# carte.net
KiCad netlist of a schematic drawn in Altium Designer
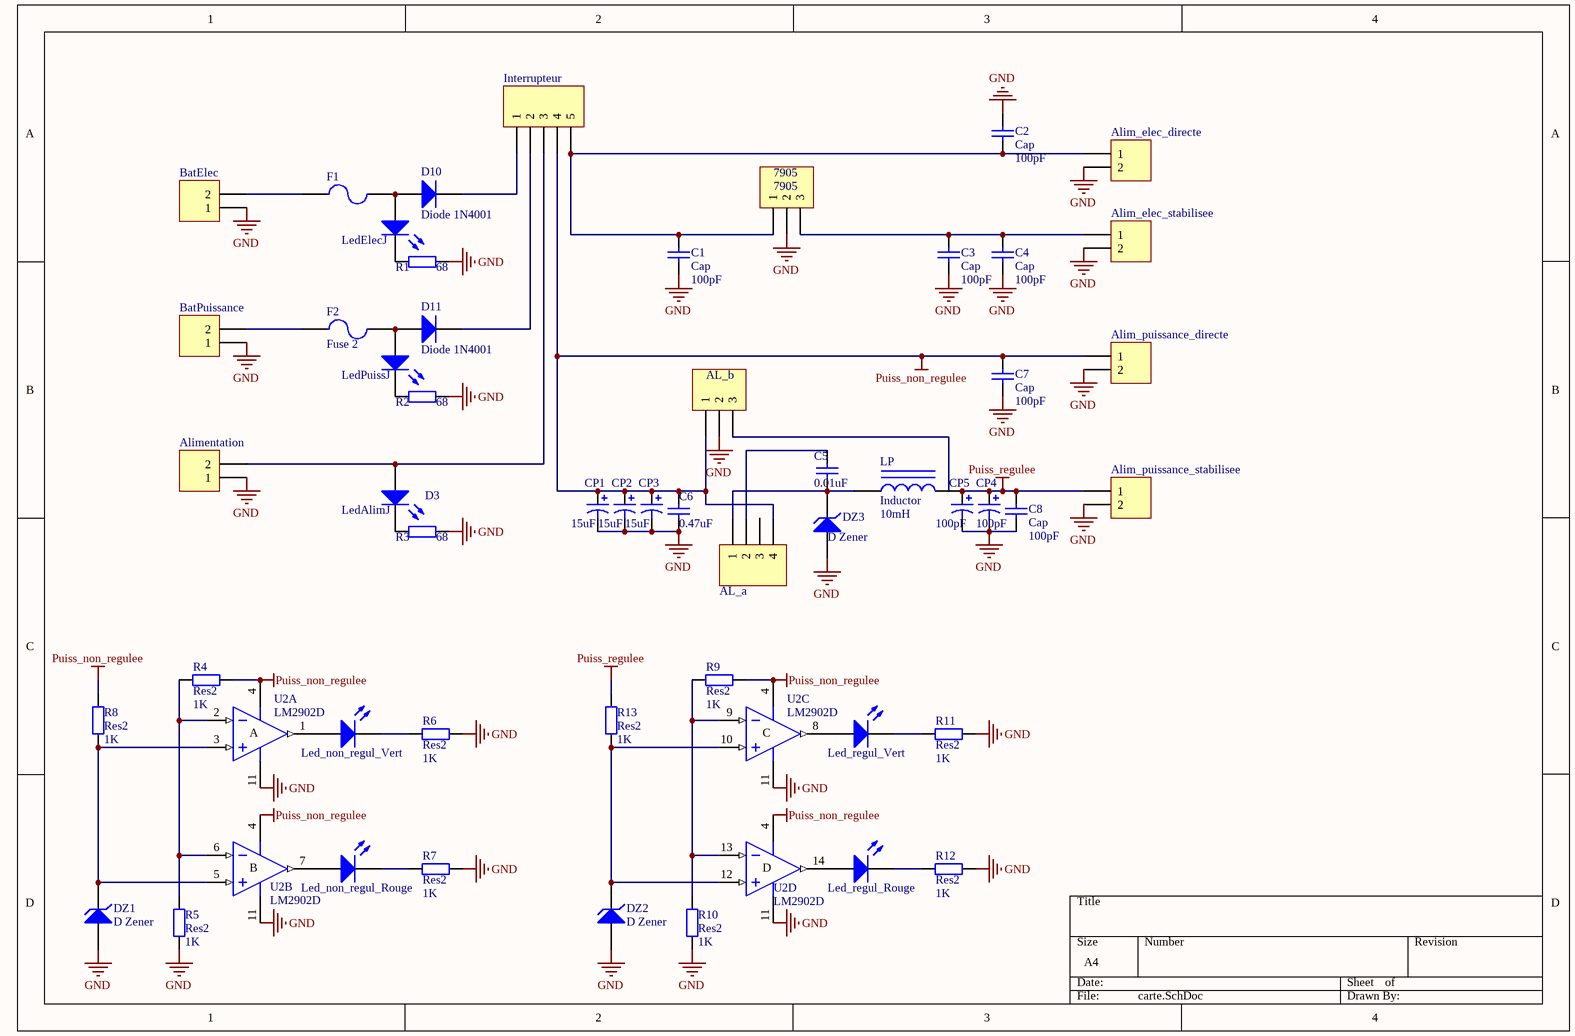
[diagram p0: carte.SchDoc]

(export (version "E")
  (design (tool "Eeschema 10.0.6"))
  (components
    (comp (ref "7905")
      (value "7905")
      (footprint "MHDR1X3")
      (description "Header, 3-Pin")
      (fields (field (name "PUBLISHER") "Altium Limited"))
      (libsource (lib "Miscellaneous Connectors") (part "MHDR1X3"))
    )
    (comp (ref "Alimentation")
      (value "Header 2")
      (footprint "HDR1X2")
      (description "Header, 2-Pin")
      (fields (field (name "PUBLISHER") "Altium Limited"))
      (libsource (lib "") (part "Header 2_1"))
    )
    (comp (ref "Alim_elec_directe")
      (value "Header 2")
      (footprint "HDR1X2")
      (description "Header, 2-Pin")
      (fields (field (name "PUBLISHER") "Altium Limited"))
      (libsource (lib "Miscellaneous Connectors") (part "Header 2"))
    )
    (comp (ref "Alim_elec_stabilisee")
      (value "Header 2")
      (footprint "HDR1X2")
      (description "Header, 2-Pin")
      (fields (field (name "PUBLISHER") "Altium Limited"))
      (libsource (lib "Miscellaneous Connectors") (part "Header 2"))
    )
    (comp (ref "Alim_puissance_directe")
      (value "Header 2")
      (footprint "HDR1X2")
      (description "Header, 2-Pin")
      (fields (field (name "PUBLISHER") "Altium Limited"))
      (libsource (lib "Miscellaneous Connectors") (part "Header 2"))
    )
    (comp (ref "Alim_puissance_stabilisee")
      (value "Header 2")
      (footprint "HDR1X2")
      (description "Header, 2-Pin")
      (fields (field (name "PUBLISHER") "Altium Limited"))
      (libsource (lib "Miscellaneous Connectors") (part "Header 2"))
    )
    (comp (ref "AL_a")
      (value "Header 4")
      (footprint "HDR1X4")
      (description "Header, 4-Pin")
      (fields (field (name "PUBLISHER") "Altium Limited"))
      (libsource (lib "Miscellaneous Connectors") (part "Header 4"))
    )
    (comp (ref "AL_b")
      (value "Header 3")
      (footprint "HDR1X3")
      (description "Header, 3-Pin")
      (fields (field (name "PUBLISHER") "Altium Limited"))
      (libsource (lib "Miscellaneous Connectors") (part "Header 3"))
    )
    (comp (ref "BatElec")
      (value "Header 2")
      (footprint "HDR1X2")
      (description "Header, 2-Pin")
      (fields (field (name "PUBLISHER") "Altium Limited"))
      (libsource (lib "") (part "Header 2_1"))
    )
    (comp (ref "BatPuissance")
      (value "Header 2")
      (footprint "HDR1X2")
      (description "Header, 2-Pin")
      (fields (field (name "PUBLISHER") "Altium Limited"))
      (libsource (lib "") (part "Header 2_1"))
    )
    (comp (ref "C1")
      (value "Cap")
      (footprint "RAD-0.3")
      (description "Capacitor")
      (fields (field (name "ALTIUM_VALUE") "100pF") (field (name "PUBLISHER") "Altium Limited"))
      (libsource (lib "Miscellaneous Devices") (part "Cap"))
    )
    (comp (ref "C2")
      (value "Cap")
      (footprint "RAD-0.3")
      (description "Capacitor")
      (fields (field (name "ALTIUM_VALUE") "100pF") (field (name "PUBLISHER") "Altium Limited"))
      (libsource (lib "Miscellaneous Devices") (part "Cap"))
    )
    (comp (ref "C3")
      (value "Cap")
      (footprint "RAD-0.3")
      (description "Capacitor")
      (fields (field (name "ALTIUM_VALUE") "100pF") (field (name "PUBLISHER") "Altium Limited"))
      (libsource (lib "Miscellaneous Devices") (part "Cap"))
    )
    (comp (ref "C4")
      (value "Cap")
      (footprint "RAD-0.3")
      (description "Capacitor")
      (fields (field (name "ALTIUM_VALUE") "100pF") (field (name "PUBLISHER") "Altium Limited"))
      (libsource (lib "Miscellaneous Devices") (part "Cap"))
    )
    (comp (ref "C5")
      (value "0.01uF")
      (footprint "RAD-0.3")
      (description "Capacitor")
      (fields (field (name "Comment") "Cap") (field (name "PUBLISHER") "Altium Limited"))
      (libsource (lib "Miscellaneous Devices") (part "Cap"))
    )
    (comp (ref "C6")
      (value "0.47uF")
      (footprint "RAD-0.3")
      (description "Capacitor")
      (fields (field (name "Comment") "Cap") (field (name "PUBLISHER") "Altium Limited"))
      (libsource (lib "Miscellaneous Devices") (part "Cap"))
    )
    (comp (ref "C7")
      (value "Cap")
      (footprint "RAD-0.3")
      (description "Capacitor")
      (fields (field (name "ALTIUM_VALUE") "100pF") (field (name "PUBLISHER") "Altium Limited"))
      (libsource (lib "Miscellaneous Devices") (part "Cap"))
    )
    (comp (ref "C8")
      (value "Cap")
      (footprint "RAD-0.3")
      (description "Capacitor")
      (fields (field (name "ALTIUM_VALUE") "100pF") (field (name "PUBLISHER") "Altium Limited"))
      (libsource (lib "Miscellaneous Devices") (part "Cap"))
    )
    (comp (ref "CP1")
      (value "15uF")
      (footprint "RB7.6-15")
      (description "Polarized Capacitor (Radial)")
      (fields (field (name "Comment") "Cap Pol1") (field (name "PUBLISHER") "Altium Limited"))
      (libsource (lib "Miscellaneous Devices") (part "Cap Pol1"))
    )
    (comp (ref "CP2")
      (value "15uF")
      (footprint "RB7.6-15")
      (description "Polarized Capacitor (Radial)")
      (fields (field (name "Comment") "Cap Pol1") (field (name "PUBLISHER") "Altium Limited"))
      (libsource (lib "Miscellaneous Devices") (part "Cap Pol1"))
    )
    (comp (ref "CP3")
      (value "15uF")
      (footprint "RB7.6-15")
      (description "Polarized Capacitor (Radial)")
      (fields (field (name "Comment") "Cap Pol1") (field (name "PUBLISHER") "Altium Limited"))
      (libsource (lib "Miscellaneous Devices") (part "Cap Pol1"))
    )
    (comp (ref "CP4")
      (value "100pF")
      (footprint "RB7.6-15")
      (description "Polarized Capacitor (Radial)")
      (fields (field (name "Comment") "Cap Pol1") (field (name "PUBLISHER") "Altium Limited"))
      (libsource (lib "Miscellaneous Devices") (part "Cap Pol1"))
    )
    (comp (ref "CP5")
      (value "100pF")
      (footprint "RB7.6-15")
      (description "Polarized Capacitor (Radial)")
      (fields (field (name "Comment") "Cap Pol1") (field (name "PUBLISHER") "Altium Limited"))
      (libsource (lib "Miscellaneous Devices") (part "Cap Pol1"))
    )
    (comp (ref "D3")
      (value "LedAlimJ")
      (footprint "LED-1")
      (description "Typical RED GaAs LED")
      (fields (field (name "PUBLISHER") "Altium Limited"))
      (libsource (lib "Miscellaneous Devices") (part "LED1"))
    )
    (comp (ref "D10")
      (value "Diode 1N4001")
      (footprint "DO-41")
      (description "1 Amp General Purpose Rectifier")
      (fields (field (name "PUBLISHER") "Altium Limited"))
      (libsource (lib "Miscellaneous Devices") (part "Diode 1N4001"))
    )
    (comp (ref "D11")
      (value "Diode 1N4001")
      (footprint "DO-41")
      (description "1 Amp General Purpose Rectifier")
      (fields (field (name "PUBLISHER") "Altium Limited"))
      (libsource (lib "Miscellaneous Devices") (part "Diode 1N4001"))
    )
    (comp (ref "DZ1")
      (value "D Zener")
      (footprint "DIODE-0.7")
      (description "Zener Diode")
      (fields (field (name "PUBLISHER") "Altium Limited"))
      (libsource (lib "Miscellaneous Devices") (part "D Zener"))
    )
    (comp (ref "DZ2")
      (value "D Zener")
      (footprint "DIODE-0.7")
      (description "Zener Diode")
      (fields (field (name "PUBLISHER") "Altium Limited"))
      (libsource (lib "Miscellaneous Devices") (part "D Zener"))
    )
    (comp (ref "DZ3")
      (value "D Zener")
      (footprint "DIODE-0.7")
      (description "Zener Diode")
      (fields (field (name "PUBLISHER") "Altium Limited"))
      (libsource (lib "Miscellaneous Devices") (part "D Zener"))
    )
    (comp (ref "F1")
      (value "Fuse 2")
      (footprint "PIN-W2/E2.8")
      (description "Fuse")
      (fields (field (name "PUBLISHER") "Altium Limited"))
      (libsource (lib "Miscellaneous Devices") (part "Fuse 2"))
    )
    (comp (ref "F2")
      (value "Fuse 2")
      (footprint "PIN-W2/E2.8")
      (description "Fuse")
      (fields (field (name "PUBLISHER") "Altium Limited"))
      (libsource (lib "Miscellaneous Devices") (part "Fuse 2"))
    )
    (comp (ref "Interrupteur")
      (value "Header 5")
      (footprint "HDR1X5")
      (description "Header, 5-Pin")
      (fields (field (name "PUBLISHER") "Altium Limited"))
      (libsource (lib "Miscellaneous Connectors") (part "Header 5"))
    )
    (comp (ref "LedElecJ")
      (value "LED1")
      (footprint "LED-1")
      (description "Typical RED GaAs LED")
      (fields (field (name "PUBLISHER") "Altium Limited"))
      (libsource (lib "Miscellaneous Devices") (part "LED1"))
    )
    (comp (ref "LedPuissJ")
      (value "LED1")
      (footprint "LED-1")
      (description "Typical RED GaAs LED")
      (fields (field (name "PUBLISHER") "Altium Limited"))
      (libsource (lib "Miscellaneous Devices") (part "LED1"))
    )
    (comp (ref "Led_non_regul_Rouge")
      (value "LED1")
      (footprint "LED-1")
      (description "Typical RED GaAs LED")
      (fields (field (name "PUBLISHER") "Altium Limited"))
      (libsource (lib "Miscellaneous Devices") (part "LED1"))
    )
    (comp (ref "Led_non_regul_Vert")
      (value "LED1")
      (footprint "LED-1")
      (description "Typical RED GaAs LED")
      (fields (field (name "PUBLISHER") "Altium Limited"))
      (libsource (lib "Miscellaneous Devices") (part "LED1"))
    )
    (comp (ref "Led_regul_Rouge")
      (value "LED1")
      (footprint "LED-1")
      (description "Typical RED GaAs LED")
      (fields (field (name "PUBLISHER") "Altium Limited"))
      (libsource (lib "Miscellaneous Devices") (part "LED1"))
    )
    (comp (ref "Led_regul_Vert")
      (value "LED1")
      (footprint "LED-1")
      (description "Typical RED GaAs LED")
      (fields (field (name "PUBLISHER") "Altium Limited"))
      (libsource (lib "Miscellaneous Devices") (part "LED1"))
    )
    (comp (ref "LP")
      (value "Inductor")
      (footprint "AXIAL-0.9")
      (description "Magnetic-Core Inductor")
      (fields (field (name "ALTIUM_VALUE") "10mH") (field (name "PUBLISHER") "Altium Limited"))
      (libsource (lib "Miscellaneous Devices") (part "Inductor Iron"))
    )
    (comp (ref "R1")
      (value "68")
      (footprint "AXIAL-0.4")
      (description "Resistor")
      (fields (field (name "Comment") "Res2") (field (name "PUBLISHER") "Altium Limited"))
      (libsource (lib "Miscellaneous Devices") (part "Res2"))
    )
    (comp (ref "R2")
      (value "68")
      (footprint "AXIAL-0.4")
      (description "Resistor")
      (fields (field (name "Comment") "Res2") (field (name "PUBLISHER") "Altium Limited"))
      (libsource (lib "Miscellaneous Devices") (part "Res2"))
    )
    (comp (ref "R3")
      (value "68")
      (footprint "AXIAL-0.4")
      (description "Resistor")
      (fields (field (name "Comment") "Res2") (field (name "PUBLISHER") "Altium Limited"))
      (libsource (lib "Miscellaneous Devices") (part "Res2"))
    )
    (comp (ref "R4")
      (value "Res2")
      (footprint "AXIAL-0.4")
      (description "Resistor")
      (fields (field (name "ALTIUM_VALUE") "1K") (field (name "PUBLISHER") "Altium Limited"))
      (libsource (lib "") (part "Res2_1"))
    )
    (comp (ref "R5")
      (value "Res2")
      (footprint "AXIAL-0.4")
      (description "Resistor")
      (fields (field (name "ALTIUM_VALUE") "1K") (field (name "PUBLISHER") "Altium Limited"))
      (libsource (lib "") (part "Res2_2"))
    )
    (comp (ref "R6")
      (value "Res2")
      (footprint "AXIAL-0.4")
      (description "Resistor")
      (fields (field (name "ALTIUM_VALUE") "1K") (field (name "PUBLISHER") "Altium Limited"))
      (libsource (lib "Miscellaneous Devices") (part "Res2"))
    )
    (comp (ref "R7")
      (value "Res2")
      (footprint "AXIAL-0.4")
      (description "Resistor")
      (fields (field (name "ALTIUM_VALUE") "1K") (field (name "PUBLISHER") "Altium Limited"))
      (libsource (lib "Miscellaneous Devices") (part "Res2"))
    )
    (comp (ref "R8")
      (value "Res2")
      (footprint "AXIAL-0.4")
      (description "Resistor")
      (fields (field (name "ALTIUM_VALUE") "1K") (field (name "PUBLISHER") "Altium Limited"))
      (libsource (lib "") (part "Res2_2"))
    )
    (comp (ref "R9")
      (value "Res2")
      (footprint "AXIAL-0.4")
      (description "Resistor")
      (fields (field (name "ALTIUM_VALUE") "1K") (field (name "PUBLISHER") "Altium Limited"))
      (libsource (lib "") (part "Res2_1"))
    )
    (comp (ref "R10")
      (value "Res2")
      (footprint "AXIAL-0.4")
      (description "Resistor")
      (fields (field (name "ALTIUM_VALUE") "1K") (field (name "PUBLISHER") "Altium Limited"))
      (libsource (lib "") (part "Res2_2"))
    )
    (comp (ref "R11")
      (value "Res2")
      (footprint "AXIAL-0.4")
      (description "Resistor")
      (fields (field (name "ALTIUM_VALUE") "1K") (field (name "PUBLISHER") "Altium Limited"))
      (libsource (lib "Miscellaneous Devices") (part "Res2"))
    )
    (comp (ref "R12")
      (value "Res2")
      (footprint "AXIAL-0.4")
      (description "Resistor")
      (fields (field (name "ALTIUM_VALUE") "1K") (field (name "PUBLISHER") "Altium Limited"))
      (libsource (lib "Miscellaneous Devices") (part "Res2"))
    )
    (comp (ref "R13")
      (value "Res2")
      (footprint "AXIAL-0.4")
      (description "Resistor")
      (fields (field (name "ALTIUM_VALUE") "1K") (field (name "PUBLISHER") "Altium Limited"))
      (libsource (lib "") (part "Res2_2"))
    )
    (comp (ref "U2")
      (value "LM2902D")
      (footprint "D014_N")
      (description "Quadruple Operational Amplifier")
      (fields (field (name "PUBLISHER") "Altium Limited"))
      (libsource (lib "TI Operational Amplifier") (part "LM2902D"))
    )
  )
  (nets
    (net (code "1") (name "GND") (class "Default")
      (node (ref "7905") (pin "2") (pinfunction "2_2") (pintype "passive"))
      (node (ref "AL_b") (pin "2") (pinfunction "2_2") (pintype "passive"))
      (node (ref "Alim_elec_directe") (pin "2") (pinfunction "2_2") (pintype "passive"))
      (node (ref "Alim_elec_stabilisee") (pin "2") (pinfunction "2_2") (pintype "passive"))
      (node (ref "Alim_puissance_directe") (pin "2") (pinfunction "2_2") (pintype "passive"))
      (node (ref "Alim_puissance_stabilisee") (pin "2") (pinfunction "2_2") (pintype "passive"))
      (node (ref "Alimentation") (pin "1") (pinfunction "1_1") (pintype "passive"))
      (node (ref "BatElec") (pin "1") (pinfunction "1_1") (pintype "passive"))
      (node (ref "BatPuissance") (pin "1") (pinfunction "1_1") (pintype "passive"))
      (node (ref "C1") (pin "1") (pinfunction "1_1") (pintype "passive"))
      (node (ref "C2") (pin "2") (pinfunction "2_2") (pintype "passive"))
      (node (ref "C3") (pin "1") (pinfunction "1_1") (pintype "passive"))
      (node (ref "C4") (pin "1") (pinfunction "1_1") (pintype "passive"))
      (node (ref "C6") (pin "1") (pinfunction "1_1") (pintype "passive"))
      (node (ref "C7") (pin "1") (pinfunction "1_1") (pintype "passive"))
      (node (ref "C8") (pin "1") (pinfunction "1_1") (pintype "passive"))
      (node (ref "CP1") (pin "2") (pinfunction "2_2") (pintype "passive"))
      (node (ref "CP2") (pin "2") (pinfunction "2_2") (pintype "passive"))
      (node (ref "CP3") (pin "2") (pinfunction "2_2") (pintype "passive"))
      (node (ref "CP4") (pin "2") (pinfunction "2_2") (pintype "passive"))
      (node (ref "CP5") (pin "2") (pinfunction "2_2") (pintype "passive"))
      (node (ref "DZ1") (pin "1") (pinfunction "A_1") (pintype "passive"))
      (node (ref "DZ2") (pin "1") (pinfunction "A_1") (pintype "passive"))
      (node (ref "DZ3") (pin "1") (pinfunction "A_1") (pintype "passive"))
      (node (ref "R1") (pin "2") (pinfunction "2_2") (pintype "passive"))
      (node (ref "R10") (pin "1") (pinfunction "1_1") (pintype "passive"))
      (node (ref "R11") (pin "2") (pinfunction "2_2") (pintype "passive"))
      (node (ref "R12") (pin "2") (pinfunction "2_2") (pintype "passive"))
      (node (ref "R2") (pin "2") (pinfunction "2_2") (pintype "passive"))
      (node (ref "R3") (pin "2") (pinfunction "2_2") (pintype "passive"))
      (node (ref "R5") (pin "1") (pinfunction "1_1") (pintype "passive"))
      (node (ref "R6") (pin "2") (pinfunction "2_2") (pintype "passive"))
      (node (ref "R7") (pin "2") (pinfunction "2_2") (pintype "passive"))
      (node (ref "U2") (pin "11") (pinfunction "V-_11") (pintype "power_in"))
    )
    (net (code "2") (name "Net-(7905-Pad1)") (class "Default")
      (node (ref "7905") (pin "1") (pinfunction "1_1") (pintype "passive"))
      (node (ref "Alim_elec_directe") (pin "1") (pinfunction "1_1") (pintype "passive"))
      (node (ref "C1") (pin "2") (pinfunction "2_2") (pintype "passive"))
      (node (ref "C2") (pin "1") (pinfunction "1_1") (pintype "passive"))
      (node (ref "Interrupteur") (pin "5") (pinfunction "5_5") (pintype "passive"))
    )
    (net (code "3") (name "Net-(7905-Pad3)") (class "Default")
      (node (ref "7905") (pin "3") (pinfunction "3_3") (pintype "passive"))
      (node (ref "Alim_elec_stabilisee") (pin "1") (pinfunction "1_1") (pintype "passive"))
      (node (ref "C3") (pin "2") (pinfunction "2_2") (pintype "passive"))
      (node (ref "C4") (pin "2") (pinfunction "2_2") (pintype "passive"))
    )
    (net (code "4") (name "Net-(AL_a-1)") (class "Default")
      (node (ref "AL_a") (pin "4") (pinfunction "1_4") (pintype "passive"))
      (node (ref "C5") (pin "1") (pinfunction "1_1") (pintype "passive"))
      (node (ref "DZ3") (pin "2") (pinfunction "K_2") (pintype "passive"))
      (node (ref "LP") (pin "1") (pinfunction "1_1") (pintype "passive"))
    )
    (net (code "5") (name "Net-(AL_a-2)") (class "Default")
      (node (ref "AL_a") (pin "3") (pinfunction "2_3") (pintype "passive"))
      (node (ref "C5") (pin "2") (pinfunction "2_2") (pintype "passive"))
    )
    (net (code "6") (name "Net-(BatElec-Pad2)") (class "Default")
      (node (ref "BatElec") (pin "2") (pinfunction "2_2") (pintype "passive"))
      (node (ref "F1") (pin "1") (pinfunction "1_1") (pintype "passive"))
    )
    (net (code "7") (name "Net-(BatPuissance-Pad2)") (class "Default")
      (node (ref "BatPuissance") (pin "2") (pinfunction "2_2") (pintype "passive"))
      (node (ref "F2") (pin "1") (pinfunction "1_1") (pintype "passive"))
    )
    (net (code "8") (name "Net-(D3-A)") (class "Default")
      (node (ref "Alimentation") (pin "2") (pinfunction "2_2") (pintype "passive"))
      (node (ref "D3") (pin "1") (pinfunction "A_1") (pintype "passive"))
      (node (ref "Interrupteur") (pin "3") (pinfunction "3_3") (pintype "passive"))
    )
    (net (code "9") (name "Net-(D3-K)") (class "Default")
      (node (ref "D3") (pin "2") (pinfunction "K_2") (pintype "passive"))
      (node (ref "R3") (pin "1") (pinfunction "1_1") (pintype "passive"))
    )
    (net (code "10") (name "Net-(D10-A)") (class "Default")
      (node (ref "D10") (pin "1") (pinfunction "A_1") (pintype "passive"))
      (node (ref "F1") (pin "2") (pinfunction "2_2") (pintype "passive"))
      (node (ref "LedElecJ") (pin "1") (pinfunction "A_1") (pintype "passive"))
    )
    (net (code "11") (name "Net-(D10-K)") (class "Default")
      (node (ref "D10") (pin "2") (pinfunction "K_2") (pintype "passive"))
      (node (ref "Interrupteur") (pin "1") (pinfunction "1_1") (pintype "passive"))
    )
    (net (code "12") (name "Net-(D11-A)") (class "Default")
      (node (ref "D11") (pin "1") (pinfunction "A_1") (pintype "passive"))
      (node (ref "F2") (pin "2") (pinfunction "2_2") (pintype "passive"))
      (node (ref "LedPuissJ") (pin "1") (pinfunction "A_1") (pintype "passive"))
    )
    (net (code "13") (name "Net-(D11-K)") (class "Default")
      (node (ref "D11") (pin "2") (pinfunction "K_2") (pintype "passive"))
      (node (ref "Interrupteur") (pin "2") (pinfunction "2_2") (pintype "passive"))
    )
    (net (code "14") (name "Net-(DZ1-K)") (class "Default")
      (node (ref "DZ1") (pin "2") (pinfunction "K_2") (pintype "passive"))
      (node (ref "R8") (pin "1") (pinfunction "1_1") (pintype "passive"))
      (node (ref "U2") (pin "3") (pinfunction "IN+_3") (pintype "input"))
      (node (ref "U2") (pin "5") (pinfunction "IN+_5") (pintype "input"))
    )
    (net (code "15") (name "Net-(DZ2-K)") (class "Default")
      (node (ref "DZ2") (pin "2") (pinfunction "K_2") (pintype "passive"))
      (node (ref "R13") (pin "1") (pinfunction "1_1") (pintype "passive"))
      (node (ref "U2") (pin "10") (pinfunction "IN+_10") (pintype "input"))
      (node (ref "U2") (pin "12") (pinfunction "IN+_12") (pintype "input"))
    )
    (net (code "16") (name "Net-(LedElecJ-K)") (class "Default")
      (node (ref "LedElecJ") (pin "2") (pinfunction "K_2") (pintype "passive"))
      (node (ref "R1") (pin "1") (pinfunction "1_1") (pintype "passive"))
    )
    (net (code "17") (name "Net-(LedPuissJ-K)") (class "Default")
      (node (ref "LedPuissJ") (pin "2") (pinfunction "K_2") (pintype "passive"))
      (node (ref "R2") (pin "1") (pinfunction "1_1") (pintype "passive"))
    )
    (net (code "18") (name "Net-(Led_non_regul_Rouge-A)") (class "Default")
      (node (ref "Led_non_regul_Rouge") (pin "1") (pinfunction "A_1") (pintype "passive"))
      (node (ref "U2") (pin "7") (pinfunction "OUT_7") (pintype "output"))
    )
    (net (code "19") (name "Net-(Led_non_regul_Rouge-K)") (class "Default")
      (node (ref "Led_non_regul_Rouge") (pin "2") (pinfunction "K_2") (pintype "passive"))
      (node (ref "R7") (pin "1") (pinfunction "1_1") (pintype "passive"))
    )
    (net (code "20") (name "Net-(Led_non_regul_Vert-A)") (class "Default")
      (node (ref "Led_non_regul_Vert") (pin "1") (pinfunction "A_1") (pintype "passive"))
      (node (ref "U2") (pin "1") (pinfunction "OUT_1") (pintype "output"))
    )
    (net (code "21") (name "Net-(Led_non_regul_Vert-K)") (class "Default")
      (node (ref "Led_non_regul_Vert") (pin "2") (pinfunction "K_2") (pintype "passive"))
      (node (ref "R6") (pin "1") (pinfunction "1_1") (pintype "passive"))
    )
    (net (code "22") (name "Net-(Led_regul_Rouge-A)") (class "Default")
      (node (ref "Led_regul_Rouge") (pin "1") (pinfunction "A_1") (pintype "passive"))
      (node (ref "U2") (pin "14") (pinfunction "OUT_14") (pintype "output"))
    )
    (net (code "23") (name "Net-(Led_regul_Rouge-K)") (class "Default")
      (node (ref "Led_regul_Rouge") (pin "2") (pinfunction "K_2") (pintype "passive"))
      (node (ref "R12") (pin "1") (pinfunction "1_1") (pintype "passive"))
    )
    (net (code "24") (name "Net-(Led_regul_Vert-A)") (class "Default")
      (node (ref "Led_regul_Vert") (pin "1") (pinfunction "A_1") (pintype "passive"))
      (node (ref "U2") (pin "8") (pinfunction "OUT_8") (pintype "output"))
    )
    (net (code "25") (name "Net-(Led_regul_Vert-K)") (class "Default")
      (node (ref "Led_regul_Vert") (pin "2") (pinfunction "K_2") (pintype "passive"))
      (node (ref "R11") (pin "1") (pinfunction "1_1") (pintype "passive"))
    )
    (net (code "26") (name "Net-(U2A-IN-)") (class "Default")
      (node (ref "R4") (pin "2") (pinfunction "2_2") (pintype "passive"))
      (node (ref "R5") (pin "2") (pinfunction "2_2") (pintype "passive"))
      (node (ref "U2") (pin "2") (pinfunction "IN-_2") (pintype "input"))
      (node (ref "U2") (pin "6") (pinfunction "IN-_6") (pintype "input"))
    )
    (net (code "27") (name "Net-(U2C-IN-)") (class "Default")
      (node (ref "R10") (pin "2") (pinfunction "2_2") (pintype "passive"))
      (node (ref "R9") (pin "2") (pinfunction "2_2") (pintype "passive"))
      (node (ref "U2") (pin "13") (pinfunction "IN-_13") (pintype "input"))
      (node (ref "U2") (pin "9") (pinfunction "IN-_9") (pintype "input"))
    )
    (net (code "28") (name "Puiss_non_regulee") (class "Default")
      (node (ref "AL_a") (pin "1") (pinfunction "4_1") (pintype "passive"))
      (node (ref "AL_b") (pin "1") (pinfunction "1_1") (pintype "passive"))
      (node (ref "Alim_puissance_directe") (pin "1") (pinfunction "1_1") (pintype "passive"))
      (node (ref "C6") (pin "2") (pinfunction "2_2") (pintype "passive"))
      (node (ref "C7") (pin "2") (pinfunction "2_2") (pintype "passive"))
      (node (ref "CP1") (pin "1") (pinfunction "1_1") (pintype "passive"))
      (node (ref "CP2") (pin "1") (pinfunction "1_1") (pintype "passive"))
      (node (ref "CP3") (pin "1") (pinfunction "1_1") (pintype "passive"))
      (node (ref "Interrupteur") (pin "4") (pinfunction "4_4") (pintype "passive"))
      (node (ref "R4") (pin "1") (pinfunction "1_1") (pintype "passive"))
      (node (ref "R8") (pin "2") (pinfunction "2_2") (pintype "passive"))
      (node (ref "R9") (pin "1") (pinfunction "1_1") (pintype "passive"))
      (node (ref "U2") (pin "4") (pinfunction "V+_4") (pintype "power_in"))
    )
    (net (code "29") (name "Puiss_regulee") (class "Default")
      (node (ref "Alim_puissance_stabilisee") (pin "1") (pinfunction "1_1") (pintype "passive"))
      (node (ref "C8") (pin "2") (pinfunction "2_2") (pintype "passive"))
      (node (ref "CP4") (pin "1") (pinfunction "1_1") (pintype "passive"))
      (node (ref "CP5") (pin "1") (pinfunction "1_1") (pintype "passive"))
      (node (ref "LP") (pin "2") (pinfunction "2_2") (pintype "passive"))
      (node (ref "R13") (pin "2") (pinfunction "2_2") (pintype "passive"))
    )
    (net (code "30") (name "unconnected-(AL_a-3-Pad2)") (class "Default")
      (node (ref "AL_a") (pin "2") (pinfunction "3_2") (pintype "passive"))
    )
    (net (code "31") (name "unconnected-(AL_b-Pad3)") (class "Default")
      (node (ref "AL_b") (pin "3") (pinfunction "3_3") (pintype "passive"))
    )
  )
)
